# display_adapter.net
KiCad netlist of a schematic drawn in EAGLE
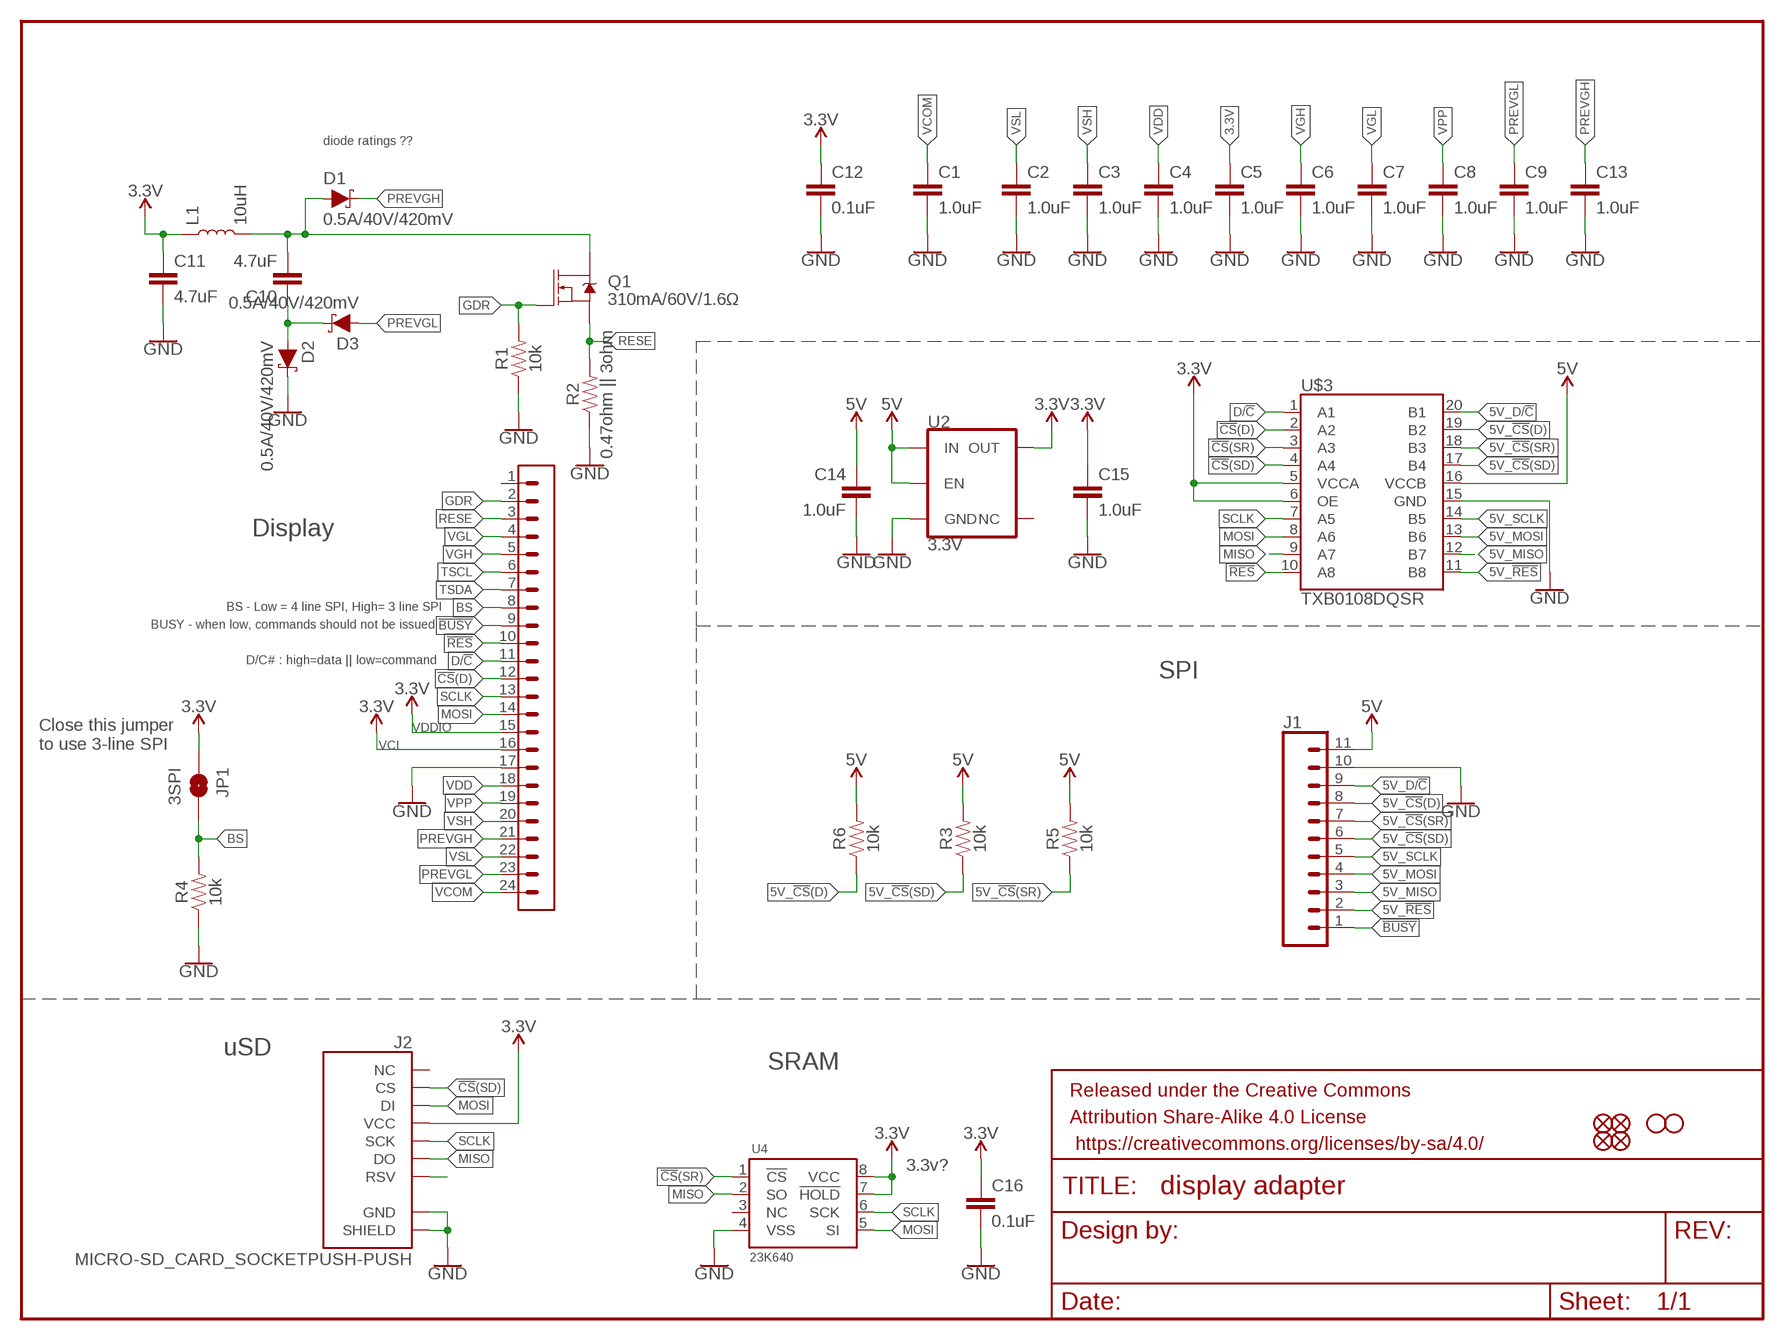
[diagram p0: schematic, sheet 1]

(export (version "E")
  (design (tool "Eeschema 10.0.6"))
  (components
    (comp (ref "C1")
      (value "1.0uF")
      (footprint "eagle-import:0603")
      (libsource (lib "eagle-import") (part "1.0UF-0603-16V-10%"))
    )
    (comp (ref "C2")
      (value "1.0uF")
      (footprint "eagle-import:0805")
      (libsource (lib "eagle-import") (part "1.0UF-0805-25V-10%"))
    )
    (comp (ref "C3")
      (value "1.0uF")
      (footprint "eagle-import:0805")
      (libsource (lib "eagle-import") (part "1.0UF-0805-25V-10%"))
    )
    (comp (ref "C4")
      (value "1.0uF")
      (footprint "eagle-import:0805")
      (libsource (lib "eagle-import") (part "1.0UF-0805-25V-10%"))
    )
    (comp (ref "C5")
      (value "1.0uF")
      (footprint "eagle-import:0805")
      (libsource (lib "eagle-import") (part "1.0UF-0805-25V-10%"))
    )
    (comp (ref "C6")
      (value "1.0uF")
      (footprint "eagle-import:0805")
      (libsource (lib "eagle-import") (part "1.0UF-0805-25V-10%"))
    )
    (comp (ref "C7")
      (value "1.0uF")
      (footprint "eagle-import:0805")
      (libsource (lib "eagle-import") (part "1.0UF-0805-25V-10%"))
    )
    (comp (ref "C8")
      (value "1.0uF")
      (footprint "eagle-import:0805")
      (libsource (lib "eagle-import") (part "1.0UF-0805-25V-10%"))
    )
    (comp (ref "C9")
      (value "1.0uF")
      (footprint "eagle-import:0805")
      (libsource (lib "eagle-import") (part "1.0UF-0805-25V-10%"))
    )
    (comp (ref "C10")
      (value "4.7uF")
      (footprint "eagle-import:0805")
      (libsource (lib "eagle-import") (part "22UF-0805-6.3V-20%"))
    )
    (comp (ref "C11")
      (value "4.7uF")
      (footprint "eagle-import:0805")
      (libsource (lib "eagle-import") (part "22UF-0805-6.3V-20%"))
    )
    (comp (ref "C12")
      (value "0.1uF")
      (footprint "eagle-import:0603")
      (libsource (lib "eagle-import") (part "0.1UF-0603-25V-(+80/-20%)"))
    )
    (comp (ref "C13")
      (value "1.0uF")
      (footprint "eagle-import:0805")
      (libsource (lib "eagle-import") (part "1.0UF-0805-25V-10%"))
    )
    (comp (ref "C14")
      (value "1.0uF")
      (footprint "eagle-import:0603")
      (libsource (lib "eagle-import") (part "1.0UF-0603-16V-10%"))
    )
    (comp (ref "C15")
      (value "1.0uF")
      (footprint "eagle-import:0603")
      (libsource (lib "eagle-import") (part "1.0UF-0603-16V-10%"))
    )
    (comp (ref "C16")
      (value "0.1uF")
      (footprint "eagle-import:0603")
      (libsource (lib "eagle-import") (part "0.1UF-0603-25V-(+80/-20%)"))
    )
    (comp (ref "D1")
      (value "0.5A/40V/420mV")
      (footprint "eagle-import:SOD-323")
      (libsource (lib "eagle-import") (part "DIODE-SCHOTTKY-PMEG4005EJ"))
    )
    (comp (ref "D2")
      (value "0.5A/40V/420mV")
      (footprint "eagle-import:SOD-323")
      (libsource (lib "eagle-import") (part "DIODE-SCHOTTKY-PMEG4005EJ"))
    )
    (comp (ref "D3")
      (value "0.5A/40V/420mV")
      (footprint "eagle-import:SOD-323")
      (libsource (lib "eagle-import") (part "DIODE-SCHOTTKY-PMEG4005EJ"))
    )
    (comp (ref "FD1")
      (value "FIDUCIALUFIDUCIAL")
      (footprint "eagle-import:FIDUCIAL-MICRO")
      (libsource (lib "eagle-import") (part "FIDUCIALUFIDUCIAL"))
    )
    (comp (ref "FD2")
      (value "FIDUCIALUFIDUCIAL")
      (footprint "eagle-import:FIDUCIAL-MICRO")
      (libsource (lib "eagle-import") (part "FIDUCIALUFIDUCIAL"))
    )
    (comp (ref "FD3")
      (value "FIDUCIALUFIDUCIAL")
      (footprint "eagle-import:FIDUCIAL-MICRO")
      (libsource (lib "eagle-import") (part "FIDUCIALUFIDUCIAL"))
    )
    (comp (ref "FD4")
      (value "FIDUCIALUFIDUCIAL")
      (footprint "eagle-import:FIDUCIAL-MICRO")
      (libsource (lib "eagle-import") (part "FIDUCIALUFIDUCIAL"))
    )
    (comp (ref "FRAME1")
      (value "FRAME-LETTER")
      (footprint "eagle-import:CREATIVE_COMMONS")
      (libsource (lib "eagle-import") (part "FRAME-LETTER"))
    )
    (comp (ref "H1")
      (value "STAND-OFF")
      (footprint "eagle-import:STAND-OFF")
      (libsource (lib "eagle-import") (part "STAND-OFF"))
    )
    (comp (ref "H2")
      (value "STAND-OFF")
      (footprint "eagle-import:STAND-OFF")
      (libsource (lib "eagle-import") (part "STAND-OFF"))
    )
    (comp (ref "J1")
      (value "CONN_111X11_NO_SILK")
      (footprint "eagle-import:1X11_NO_SILK")
      (libsource (lib "eagle-import") (part "CONN_111X11_NO_SILK"))
    )
    (comp (ref "J2")
      (value "MICRO-SD_CARD_SOCKETPUSH-PUSH")
      (footprint "eagle-import:MICRO-SD-SOCKET")
      (libsource (lib "eagle-import") (part "MICRO-SD_CARD_SOCKETPUSH-PUSH"))
    )
    (comp (ref "JP1")
      (value "3SPI")
      (footprint "eagle-import:SMT-JUMPER_2_NO_SILK")
      (libsource (lib "eagle-import") (part "JUMPER-SMT_2_NO_SILK"))
    )
    (comp (ref "L1")
      (value "10uH")
      (footprint "eagle-import:INDUCTOR_4.7UH")
      (libsource (lib "eagle-import") (part "INDUCTOR-CDRH-10UH"))
    )
    (comp (ref "Q1")
      (value "310mA/60V/1.6Ω")
      (footprint "eagle-import:SOT323")
      (libsource (lib "eagle-import") (part "MOSFET-NCH-2N7002PW"))
    )
    (comp (ref "R1")
      (value "10k")
      (footprint "eagle-import:0603")
      (libsource (lib "eagle-import") (part "10KOHM-0603-1/10W-1%"))
    )
    (comp (ref "R2")
      (value "0.47ohm || 3ohm")
      (footprint "eagle-import:0603")
      (libsource (lib "eagle-import") (part "RESISTOR0603"))
    )
    (comp (ref "R3")
      (value "10k")
      (footprint "eagle-import:0603")
      (libsource (lib "eagle-import") (part "10KOHM-0603-1/10W-1%"))
    )
    (comp (ref "R4")
      (value "10k")
      (footprint "eagle-import:0603")
      (libsource (lib "eagle-import") (part "10KOHM-0603-1/10W-1%"))
    )
    (comp (ref "R5")
      (value "10k")
      (footprint "eagle-import:0603")
      (libsource (lib "eagle-import") (part "10KOHM-0603-1/10W-1%"))
    )
    (comp (ref "R6")
      (value "10k")
      (footprint "eagle-import:0603")
      (libsource (lib "eagle-import") (part "10KOHM-0603-1/10W-1%"))
    )
    (comp (ref "U$1")
      (value "24_PIN_FPC_0.5MM")
      (footprint "eagle-import:24_PIN_FPC_0.5MM")
      (libsource (lib "eagle-import") (part "24_PIN_FPC_0.5MM"))
    )
    (comp (ref "U$3")
      (value "TXB0108DQSR")
      (footprint "eagle-import:UFDFN-20")
      (libsource (lib "eagle-import") (part "TXB0108"))
    )
    (comp (ref "U2")
      (value "3.3V")
      (footprint "eagle-import:SOT23-5")
      (libsource (lib "eagle-import") (part "V_REG_AP2112K-3.3V"))
    )
    (comp (ref "U4")
      (value "23K640")
      (footprint "eagle-import:SOIC-8")
      (libsource (lib "eagle-import") (part "23K640"))
    )
  )
  (nets
    (net (code "1") (name "/5V_D{slash}~{C}") (class "Default")
      (node (ref "J1") (pin "9") (pinfunction "9_9") (pintype "passive"))
      (node (ref "U$3") (pin "20") (pinfunction "B1_20") (pintype "bidirectional"))
    )
    (net (code "2") (name "/5V_~{CS}(D)") (class "Default")
      (node (ref "J1") (pin "8") (pinfunction "8_8") (pintype "passive"))
      (node (ref "R6") (pin "1") (pinfunction "1_1") (pintype "passive"))
      (node (ref "U$3") (pin "19") (pinfunction "B2_19") (pintype "bidirectional"))
    )
    (net (code "3") (name "/5V_~{CS}(SD)") (class "Default")
      (node (ref "J1") (pin "6") (pinfunction "6_6") (pintype "passive"))
      (node (ref "R3") (pin "1") (pinfunction "1_1") (pintype "passive"))
      (node (ref "U$3") (pin "17") (pinfunction "B4_17") (pintype "bidirectional"))
    )
    (net (code "4") (name "/5V_~{CS}(SR)") (class "Default")
      (node (ref "J1") (pin "7") (pinfunction "7_7") (pintype "passive"))
      (node (ref "R5") (pin "1") (pinfunction "1_1") (pintype "passive"))
      (node (ref "U$3") (pin "18") (pinfunction "B3_18") (pintype "bidirectional"))
    )
    (net (code "5") (name "/5V_~{RES}") (class "Default")
      (node (ref "J1") (pin "2") (pinfunction "2_2") (pintype "passive"))
      (node (ref "U$3") (pin "11") (pinfunction "B8_11") (pintype "bidirectional"))
    )
    (net (code "6") (name "/D{slash}~{C}") (class "Default")
      (node (ref "U$1") (pin "11") (pinfunction "11_11") (pintype "bidirectional"))
      (node (ref "U$3") (pin "1") (pinfunction "A1_1") (pintype "bidirectional"))
    )
    (net (code "7") (name "/~{BUSY}") (class "Default")
      (node (ref "J1") (pin "1") (pinfunction "1_1") (pintype "passive"))
      (node (ref "U$1") (pin "9") (pinfunction "9_9") (pintype "bidirectional"))
    )
    (net (code "8") (name "/~{CS}(D)") (class "Default")
      (node (ref "U$1") (pin "12") (pinfunction "12_12") (pintype "bidirectional"))
      (node (ref "U$3") (pin "2") (pinfunction "A2_2") (pintype "bidirectional"))
    )
    (net (code "9") (name "/~{CS}(SD)") (class "Default")
      (node (ref "J2") (pin "CS") (pinfunction "CS_CS") (pintype "bidirectional"))
      (node (ref "U$3") (pin "4") (pinfunction "A4_4") (pintype "bidirectional"))
    )
    (net (code "10") (name "/~{CS}(SR)") (class "Default")
      (node (ref "U$3") (pin "3") (pinfunction "A3_3") (pintype "bidirectional"))
      (node (ref "U4") (pin "1") (pinfunction "~{CS}_1") (pintype "bidirectional"))
    )
    (net (code "11") (name "/~{RES}") (class "Default")
      (node (ref "U$1") (pin "10") (pinfunction "10_10") (pintype "bidirectional"))
      (node (ref "U$3") (pin "10") (pinfunction "A8_10") (pintype "bidirectional"))
    )
    (net (code "12") (name "3.3V") (class "Default")
      (node (ref "C11") (pin "1") (pinfunction "1_1") (pintype "passive"))
      (node (ref "C12") (pin "1") (pinfunction "1_1") (pintype "passive"))
      (node (ref "C15") (pin "1") (pinfunction "1_1") (pintype "passive"))
      (node (ref "C16") (pin "1") (pinfunction "1_1") (pintype "passive"))
      (node (ref "C5") (pin "1") (pinfunction "1_1") (pintype "passive"))
      (node (ref "J2") (pin "VCC") (pinfunction "VCC_VCC") (pintype "bidirectional"))
      (node (ref "JP1") (pin "1") (pinfunction "1_1") (pintype "passive"))
      (node (ref "L1") (pin "P$1") (pinfunction "1_P$1") (pintype "passive"))
      (node (ref "U$1") (pin "15") (pinfunction "15_15") (pintype "bidirectional"))
      (node (ref "U$1") (pin "16") (pinfunction "16_16") (pintype "bidirectional"))
      (node (ref "U$3") (pin "5") (pinfunction "VCCA_5") (pintype "bidirectional"))
      (node (ref "U$3") (pin "6") (pinfunction "OE_6") (pintype "bidirectional"))
      (node (ref "U2") (pin "5") (pinfunction "OUT_5") (pintype "passive"))
      (node (ref "U4") (pin "7") (pinfunction "~{HOLD}_7") (pintype "bidirectional"))
      (node (ref "U4") (pin "8") (pinfunction "VCC_8") (pintype "bidirectional"))
    )
    (net (code "13") (name "5V") (class "Default")
      (node (ref "C14") (pin "1") (pinfunction "1_1") (pintype "passive"))
      (node (ref "J1") (pin "11") (pinfunction "11_11") (pintype "passive"))
      (node (ref "R3") (pin "2") (pinfunction "2_2") (pintype "passive"))
      (node (ref "R5") (pin "2") (pinfunction "2_2") (pintype "passive"))
      (node (ref "R6") (pin "2") (pinfunction "2_2") (pintype "passive"))
      (node (ref "U$3") (pin "16") (pinfunction "VCCB_16") (pintype "bidirectional"))
      (node (ref "U2") (pin "1") (pinfunction "IN_1") (pintype "input"))
      (node (ref "U2") (pin "3") (pinfunction "EN_3") (pintype "input"))
    )
    (net (code "14") (name "5V_MISO") (class "Default")
      (node (ref "J1") (pin "3") (pinfunction "3_3") (pintype "passive"))
      (node (ref "U$3") (pin "12") (pinfunction "B7_12") (pintype "bidirectional"))
    )
    (net (code "15") (name "5V_MOSI") (class "Default")
      (node (ref "J1") (pin "4") (pinfunction "4_4") (pintype "passive"))
      (node (ref "U$3") (pin "13") (pinfunction "B6_13") (pintype "bidirectional"))
    )
    (net (code "16") (name "5V_SCLK") (class "Default")
      (node (ref "J1") (pin "5") (pinfunction "5_5") (pintype "passive"))
      (node (ref "U$3") (pin "14") (pinfunction "B5_14") (pintype "bidirectional"))
    )
    (net (code "17") (name "BS") (class "Default")
      (node (ref "JP1") (pin "2") (pinfunction "2_2") (pintype "passive"))
      (node (ref "R4") (pin "2") (pinfunction "2_2") (pintype "passive"))
      (node (ref "U$1") (pin "8") (pinfunction "8_8") (pintype "bidirectional"))
    )
    (net (code "18") (name "GDR") (class "Default")
      (node (ref "Q1") (pin "1") (pinfunction "G_1") (pintype "bidirectional"))
      (node (ref "R1") (pin "2") (pinfunction "2_2") (pintype "passive"))
      (node (ref "U$1") (pin "2") (pinfunction "2_2") (pintype "bidirectional"))
    )
    (net (code "19") (name "GND") (class "Default")
      (node (ref "C1") (pin "2") (pinfunction "2_2") (pintype "passive"))
      (node (ref "C11") (pin "2") (pinfunction "2_2") (pintype "passive"))
      (node (ref "C12") (pin "2") (pinfunction "2_2") (pintype "passive"))
      (node (ref "C13") (pin "2") (pinfunction "2_2") (pintype "passive"))
      (node (ref "C14") (pin "2") (pinfunction "2_2") (pintype "passive"))
      (node (ref "C15") (pin "2") (pinfunction "2_2") (pintype "passive"))
      (node (ref "C16") (pin "2") (pinfunction "2_2") (pintype "passive"))
      (node (ref "C2") (pin "2") (pinfunction "2_2") (pintype "passive"))
      (node (ref "C3") (pin "2") (pinfunction "2_2") (pintype "passive"))
      (node (ref "C4") (pin "2") (pinfunction "2_2") (pintype "passive"))
      (node (ref "C5") (pin "2") (pinfunction "2_2") (pintype "passive"))
      (node (ref "C6") (pin "2") (pinfunction "2_2") (pintype "passive"))
      (node (ref "C7") (pin "2") (pinfunction "2_2") (pintype "passive"))
      (node (ref "C8") (pin "2") (pinfunction "2_2") (pintype "passive"))
      (node (ref "C9") (pin "2") (pinfunction "2_2") (pintype "passive"))
      (node (ref "D2") (pin "C") (pinfunction "C_C") (pintype "passive"))
      (node (ref "J1") (pin "10") (pinfunction "10_10") (pintype "passive"))
      (node (ref "J2") (pin "CD1") (pinfunction "SHIELD_CD1") (pintype "bidirectional"))
      (node (ref "J2") (pin "GND") (pinfunction "GND_GND") (pintype "bidirectional"))
      (node (ref "R1") (pin "1") (pinfunction "1_1") (pintype "passive"))
      (node (ref "R2") (pin "1") (pinfunction "1_1") (pintype "passive"))
      (node (ref "R4") (pin "1") (pinfunction "1_1") (pintype "passive"))
      (node (ref "U$1") (pin "17") (pinfunction "17_17") (pintype "bidirectional"))
      (node (ref "U$3") (pin "15") (pinfunction "GND_15") (pintype "bidirectional"))
      (node (ref "U2") (pin "2") (pinfunction "GND_2") (pintype "input"))
      (node (ref "U4") (pin "4") (pinfunction "VSS_4") (pintype "bidirectional"))
    )
    (net (code "20") (name "MISO") (class "Default")
      (node (ref "J2") (pin "DO") (pinfunction "DO_DO") (pintype "bidirectional"))
      (node (ref "U$3") (pin "9") (pinfunction "A7_9") (pintype "bidirectional"))
      (node (ref "U4") (pin "2") (pinfunction "SO_2") (pintype "bidirectional"))
    )
    (net (code "21") (name "MOSI") (class "Default")
      (node (ref "J2") (pin "DI") (pinfunction "DI_DI") (pintype "bidirectional"))
      (node (ref "U$1") (pin "14") (pinfunction "14_14") (pintype "bidirectional"))
      (node (ref "U$3") (pin "8") (pinfunction "A6_8") (pintype "bidirectional"))
      (node (ref "U4") (pin "5") (pinfunction "SI_5") (pintype "bidirectional"))
    )
    (net (code "22") (name "Net-(C10-Pad1)") (class "Default")
      (node (ref "C10") (pin "1") (pinfunction "1_1") (pintype "passive"))
      (node (ref "D2") (pin "A") (pinfunction "A_A") (pintype "passive"))
      (node (ref "D3") (pin "C") (pinfunction "C_C") (pintype "passive"))
    )
    (net (code "23") (name "Net-(L1-2)") (class "Default")
      (node (ref "C10") (pin "2") (pinfunction "2_2") (pintype "passive"))
      (node (ref "D1") (pin "A") (pinfunction "A_A") (pintype "passive"))
      (node (ref "L1") (pin "P$2") (pinfunction "2_P$2") (pintype "passive"))
      (node (ref "Q1") (pin "3") (pinfunction "D_3") (pintype "bidirectional"))
    )
    (net (code "24") (name "PREVGH") (class "Default")
      (node (ref "C13") (pin "1") (pinfunction "1_1") (pintype "passive"))
      (node (ref "D1") (pin "C") (pinfunction "C_C") (pintype "passive"))
      (node (ref "U$1") (pin "21") (pinfunction "21_21") (pintype "bidirectional"))
    )
    (net (code "25") (name "PREVGL") (class "Default")
      (node (ref "C9") (pin "1") (pinfunction "1_1") (pintype "passive"))
      (node (ref "D3") (pin "A") (pinfunction "A_A") (pintype "passive"))
      (node (ref "U$1") (pin "23") (pinfunction "23_23") (pintype "bidirectional"))
    )
    (net (code "26") (name "RESE") (class "Default")
      (node (ref "Q1") (pin "2") (pinfunction "S_2") (pintype "bidirectional"))
      (node (ref "R2") (pin "2") (pinfunction "2_2") (pintype "passive"))
      (node (ref "U$1") (pin "3") (pinfunction "3_3") (pintype "bidirectional"))
    )
    (net (code "27") (name "SCLK") (class "Default")
      (node (ref "J2") (pin "SCLK") (pinfunction "SCK_SCLK") (pintype "bidirectional"))
      (node (ref "U$1") (pin "13") (pinfunction "13_13") (pintype "bidirectional"))
      (node (ref "U$3") (pin "7") (pinfunction "A5_7") (pintype "bidirectional"))
      (node (ref "U4") (pin "6") (pinfunction "SCK_6") (pintype "bidirectional"))
    )
    (net (code "28") (name "TSCL") (class "Default")
      (node (ref "U$1") (pin "6") (pinfunction "6_6") (pintype "bidirectional"))
    )
    (net (code "29") (name "TSDA") (class "Default")
      (node (ref "U$1") (pin "7") (pinfunction "7_7") (pintype "bidirectional"))
    )
    (net (code "30") (name "VCOM") (class "Default")
      (node (ref "C1") (pin "1") (pinfunction "1_1") (pintype "passive"))
      (node (ref "U$1") (pin "24") (pinfunction "24_24") (pintype "bidirectional"))
    )
    (net (code "31") (name "VDD") (class "Default")
      (node (ref "C4") (pin "1") (pinfunction "1_1") (pintype "passive"))
      (node (ref "U$1") (pin "18") (pinfunction "18_18") (pintype "bidirectional"))
    )
    (net (code "32") (name "VGH") (class "Default")
      (node (ref "C6") (pin "1") (pinfunction "1_1") (pintype "passive"))
      (node (ref "U$1") (pin "5") (pinfunction "5_5") (pintype "bidirectional"))
    )
    (net (code "33") (name "VGL") (class "Default")
      (node (ref "C7") (pin "1") (pinfunction "1_1") (pintype "passive"))
      (node (ref "U$1") (pin "4") (pinfunction "4_4") (pintype "bidirectional"))
    )
    (net (code "34") (name "VPP") (class "Default")
      (node (ref "C8") (pin "1") (pinfunction "1_1") (pintype "passive"))
      (node (ref "U$1") (pin "19") (pinfunction "19_19") (pintype "bidirectional"))
    )
    (net (code "35") (name "VSH") (class "Default")
      (node (ref "C3") (pin "1") (pinfunction "1_1") (pintype "passive"))
      (node (ref "U$1") (pin "20") (pinfunction "20_20") (pintype "bidirectional"))
    )
    (net (code "36") (name "VSL") (class "Default")
      (node (ref "C2") (pin "1") (pinfunction "1_1") (pintype "passive"))
      (node (ref "U$1") (pin "22") (pinfunction "22_22") (pintype "bidirectional"))
    )
    (net (code "37") (name "unconnected-(J2-NC-PadRSV2)") (class "Default")
      (node (ref "J2") (pin "RSV2") (pinfunction "NC_RSV2") (pintype "bidirectional"))
    )
    (net (code "38") (name "unconnected-(J2-RSV-PadRSV1)") (class "Default")
      (node (ref "J2") (pin "RSV1") (pinfunction "RSV_RSV1") (pintype "bidirectional"))
    )
    (net (code "39") (name "unconnected-(U$1-Pad1)") (class "Default")
      (node (ref "U$1") (pin "1") (pinfunction "1_1") (pintype "bidirectional"))
    )
    (net (code "40") (name "unconnected-(U2-NC-Pad4)") (class "Default")
      (node (ref "U2") (pin "4") (pinfunction "NC_4") (pintype "no_connect"))
    )
    (net (code "41") (name "unconnected-(U4-NC-Pad3)") (class "Default")
      (node (ref "U4") (pin "3") (pinfunction "NC_3") (pintype "bidirectional"))
    )
  )
)
